# PCB-Neopixel_Control.net
KiCad netlist of a schematic drawn in EAGLE
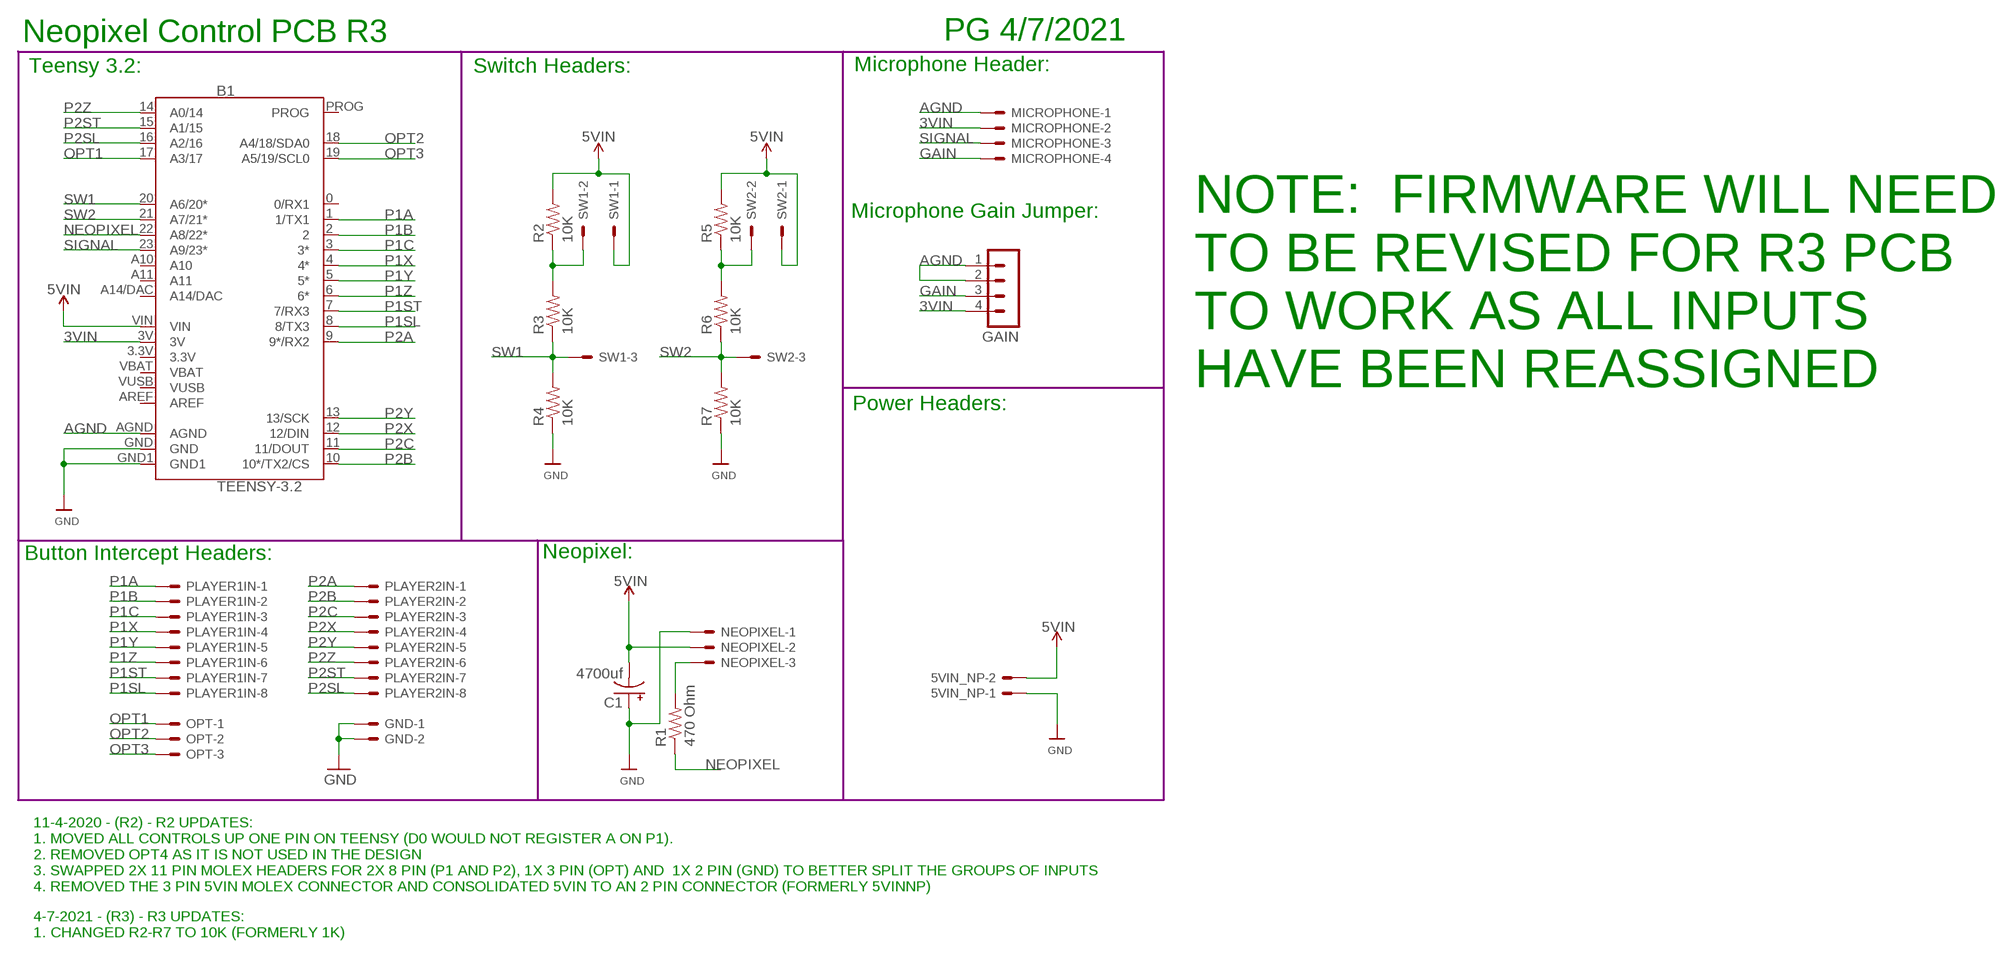
[diagram p0: schematic, sheet 1]

(export (version "E")
  (design (tool "Eeschema 10.0.6"))
  (components
    (comp (ref "5VIN_NP")
      (value "KK-156-2")
      (footprint "eagle-import:KK-156-2")
      (fields (field (name "MF") "MOLEX"))
      (libsource (lib "eagle-import") (part "KK-156-2"))
    )
    (comp (ref "B1")
      (value "TEENSY-3.2")
      (footprint "eagle-import:TEENSY-3.1")
      (libsource (lib "eagle-import") (part "TEENSY-3.1SILK"))
    )
    (comp (ref "C1")
      (value "4700uf")
      (footprint "eagle-import:E5-13")
      (libsource (lib "eagle-import") (part "CPOL-USE5-13"))
    )
    (comp (ref "GAIN")
      (value "MA04-1")
      (footprint "eagle-import:MA04-1")
      (libsource (lib "eagle-import") (part "MA04-1"))
    )
    (comp (ref "GND")
      (value "KK-156-2")
      (footprint "eagle-import:KK-156-2")
      (fields (field (name "MF") "MOLEX"))
      (libsource (lib "eagle-import") (part "KK-156-2"))
    )
    (comp (ref "MICROPHONE")
      (value "KK-156-4")
      (footprint "eagle-import:KK-156-4")
      (fields (field (name "MF") "MOLEX"))
      (libsource (lib "eagle-import") (part "KK-156-4"))
    )
    (comp (ref "NEOPIXEL")
      (value "KK-156-3")
      (footprint "eagle-import:KK-156-3")
      (fields (field (name "MF") "MOLEX"))
      (libsource (lib "eagle-import") (part "KK-156-3"))
    )
    (comp (ref "OPT")
      (value "KK-156-3")
      (footprint "eagle-import:KK-156-3")
      (fields (field (name "MF") "MOLEX"))
      (libsource (lib "eagle-import") (part "KK-156-3"))
    )
    (comp (ref "PLAYER1IN")
      (value "KK-156-8")
      (footprint "eagle-import:KK-156-8")
      (fields (field (name "MF") "MOLEX"))
      (libsource (lib "eagle-import") (part "KK-156-8"))
    )
    (comp (ref "PLAYER2IN")
      (value "KK-156-8")
      (footprint "eagle-import:KK-156-8")
      (fields (field (name "MF") "MOLEX"))
      (libsource (lib "eagle-import") (part "KK-156-8"))
    )
    (comp (ref "R1")
      (value "470 Ohm")
      (footprint "eagle-import:R1206")
      (libsource (lib "eagle-import") (part "R-US_R1206"))
    )
    (comp (ref "R2")
      (value "10K")
      (footprint "eagle-import:R1206")
      (libsource (lib "eagle-import") (part "R-US_R1206"))
    )
    (comp (ref "R3")
      (value "10K")
      (footprint "eagle-import:R1206")
      (libsource (lib "eagle-import") (part "R-US_R1206"))
    )
    (comp (ref "R4")
      (value "10K")
      (footprint "eagle-import:R1206")
      (libsource (lib "eagle-import") (part "R-US_R1206"))
    )
    (comp (ref "R5")
      (value "10K")
      (footprint "eagle-import:R1206")
      (libsource (lib "eagle-import") (part "R-US_R1206"))
    )
    (comp (ref "R6")
      (value "10K")
      (footprint "eagle-import:R1206")
      (libsource (lib "eagle-import") (part "R-US_R1206"))
    )
    (comp (ref "R7")
      (value "10K")
      (footprint "eagle-import:R1206")
      (libsource (lib "eagle-import") (part "R-US_R1206"))
    )
    (comp (ref "SW1")
      (value "KK-156-3")
      (footprint "eagle-import:KK-156-3")
      (fields (field (name "MF") "MOLEX"))
      (libsource (lib "eagle-import") (part "KK-156-3"))
    )
    (comp (ref "SW2")
      (value "KK-156-3")
      (footprint "eagle-import:KK-156-3")
      (fields (field (name "MF") "MOLEX"))
      (libsource (lib "eagle-import") (part "KK-156-3"))
    )
  )
  (nets
    (net (code "1") (name "/3.3V") (class "Default")
      (node (ref "B1") (pin "3.3V") (pinfunction "3.3V_3.3V") (pintype "power_in"))
    )
    (net (code "2") (name "/3VIN") (class "Default")
      (node (ref "B1") (pin "3V") (pinfunction "3V_3V") (pintype "power_in"))
      (node (ref "GAIN") (pin "4") (pinfunction "4_4") (pintype "passive"))
      (node (ref "MICROPHONE") (pin "2") (pinfunction "S_2") (pintype "passive"))
    )
    (net (code "3") (name "/AGND") (class "Default")
      (node (ref "B1") (pin "AGND") (pinfunction "AGND_AGND") (pintype "power_in"))
      (node (ref "GAIN") (pin "1") (pinfunction "1_1") (pintype "passive"))
      (node (ref "GAIN") (pin "2") (pinfunction "2_2") (pintype "passive"))
      (node (ref "MICROPHONE") (pin "1") (pinfunction "S_1") (pintype "passive"))
    )
    (net (code "4") (name "/GAIN") (class "Default")
      (node (ref "GAIN") (pin "3") (pinfunction "3_3") (pintype "passive"))
      (node (ref "MICROPHONE") (pin "4") (pinfunction "S_4") (pintype "passive"))
    )
    (net (code "5") (name "/NEOPIXEL") (class "Default")
      (node (ref "B1") (pin "22") (pinfunction "A8/22*_22") (pintype "bidirectional"))
      (node (ref "R1") (pin "1") (pinfunction "1_1") (pintype "passive"))
    )
    (net (code "6") (name "/OPT1") (class "Default")
      (node (ref "B1") (pin "17") (pinfunction "A3/17_17") (pintype "bidirectional"))
      (node (ref "OPT") (pin "1") (pinfunction "S_1") (pintype "passive"))
    )
    (net (code "7") (name "/OPT2") (class "Default")
      (node (ref "B1") (pin "18") (pinfunction "A4/18/SDA0_18") (pintype "bidirectional"))
      (node (ref "OPT") (pin "2") (pinfunction "S_2") (pintype "passive"))
    )
    (net (code "8") (name "/OPT3") (class "Default")
      (node (ref "B1") (pin "19") (pinfunction "A5/19/SCL0_19") (pintype "bidirectional"))
      (node (ref "OPT") (pin "3") (pinfunction "S_3") (pintype "passive"))
    )
    (net (code "9") (name "/P1A") (class "Default")
      (node (ref "B1") (pin "1") (pinfunction "1/TX1_1") (pintype "bidirectional"))
      (node (ref "PLAYER1IN") (pin "1") (pinfunction "S_1") (pintype "passive"))
    )
    (net (code "10") (name "/P1B") (class "Default")
      (node (ref "B1") (pin "2") (pinfunction "2_2") (pintype "bidirectional"))
      (node (ref "PLAYER1IN") (pin "2") (pinfunction "S_2") (pintype "passive"))
    )
    (net (code "11") (name "/P1C") (class "Default")
      (node (ref "B1") (pin "3") (pinfunction "3*_3") (pintype "bidirectional"))
      (node (ref "PLAYER1IN") (pin "3") (pinfunction "S_3") (pintype "passive"))
    )
    (net (code "12") (name "/P1SL") (class "Default")
      (node (ref "B1") (pin "8") (pinfunction "8/TX3_8") (pintype "bidirectional"))
      (node (ref "PLAYER1IN") (pin "8") (pinfunction "S_8") (pintype "passive"))
    )
    (net (code "13") (name "/P1ST") (class "Default")
      (node (ref "B1") (pin "7") (pinfunction "7/RX3_7") (pintype "bidirectional"))
      (node (ref "PLAYER1IN") (pin "7") (pinfunction "S_7") (pintype "passive"))
    )
    (net (code "14") (name "/P1X") (class "Default")
      (node (ref "B1") (pin "4") (pinfunction "4*_4") (pintype "bidirectional"))
      (node (ref "PLAYER1IN") (pin "4") (pinfunction "S_4") (pintype "passive"))
    )
    (net (code "15") (name "/P1Y") (class "Default")
      (node (ref "B1") (pin "5") (pinfunction "5*_5") (pintype "bidirectional"))
      (node (ref "PLAYER1IN") (pin "5") (pinfunction "S_5") (pintype "passive"))
    )
    (net (code "16") (name "/P1Z") (class "Default")
      (node (ref "B1") (pin "6") (pinfunction "6*_6") (pintype "bidirectional"))
      (node (ref "PLAYER1IN") (pin "6") (pinfunction "S_6") (pintype "passive"))
    )
    (net (code "17") (name "/P2A") (class "Default")
      (node (ref "B1") (pin "9") (pinfunction "9*/RX2_9") (pintype "bidirectional"))
      (node (ref "PLAYER2IN") (pin "1") (pinfunction "S_1") (pintype "passive"))
    )
    (net (code "18") (name "/P2B") (class "Default")
      (node (ref "B1") (pin "10") (pinfunction "10*/TX2/CS_10") (pintype "bidirectional"))
      (node (ref "PLAYER2IN") (pin "2") (pinfunction "S_2") (pintype "passive"))
    )
    (net (code "19") (name "/P2C") (class "Default")
      (node (ref "B1") (pin "11") (pinfunction "11/DOUT_11") (pintype "bidirectional"))
      (node (ref "PLAYER2IN") (pin "3") (pinfunction "S_3") (pintype "passive"))
    )
    (net (code "20") (name "/P2SL") (class "Default")
      (node (ref "B1") (pin "16") (pinfunction "A2/16_16") (pintype "bidirectional"))
      (node (ref "PLAYER2IN") (pin "8") (pinfunction "S_8") (pintype "passive"))
    )
    (net (code "21") (name "/P2ST") (class "Default")
      (node (ref "B1") (pin "15") (pinfunction "A1/15_15") (pintype "bidirectional"))
      (node (ref "PLAYER2IN") (pin "7") (pinfunction "S_7") (pintype "passive"))
    )
    (net (code "22") (name "/P2X") (class "Default")
      (node (ref "B1") (pin "12") (pinfunction "12/DIN_12") (pintype "bidirectional"))
      (node (ref "PLAYER2IN") (pin "4") (pinfunction "S_4") (pintype "passive"))
    )
    (net (code "23") (name "/P2Y") (class "Default")
      (node (ref "B1") (pin "13") (pinfunction "13/SCK_13") (pintype "bidirectional"))
      (node (ref "PLAYER2IN") (pin "5") (pinfunction "S_5") (pintype "passive"))
    )
    (net (code "24") (name "/P2Z") (class "Default")
      (node (ref "B1") (pin "14") (pinfunction "A0/14_14") (pintype "bidirectional"))
      (node (ref "PLAYER2IN") (pin "6") (pinfunction "S_6") (pintype "passive"))
    )
    (net (code "25") (name "/SIGNAL") (class "Default")
      (node (ref "B1") (pin "23") (pinfunction "A9/23*_23") (pintype "bidirectional"))
      (node (ref "MICROPHONE") (pin "3") (pinfunction "S_3") (pintype "passive"))
    )
    (net (code "26") (name "/SW1") (class "Default")
      (node (ref "B1") (pin "20") (pinfunction "A6/20*_20") (pintype "bidirectional"))
      (node (ref "R3") (pin "1") (pinfunction "1_1") (pintype "passive"))
      (node (ref "R4") (pin "2") (pinfunction "2_2") (pintype "passive"))
      (node (ref "SW1") (pin "3") (pinfunction "S_3") (pintype "passive"))
    )
    (net (code "27") (name "/SW2") (class "Default")
      (node (ref "B1") (pin "21") (pinfunction "A7/21*_21") (pintype "bidirectional"))
      (node (ref "R6") (pin "1") (pinfunction "1_1") (pintype "passive"))
      (node (ref "R7") (pin "2") (pinfunction "2_2") (pintype "passive"))
      (node (ref "SW2") (pin "3") (pinfunction "S_3") (pintype "passive"))
    )
    (net (code "28") (name "/VBAT") (class "Default")
      (node (ref "B1") (pin "VBAT") (pinfunction "VBAT_VBAT") (pintype "power_in"))
    )
    (net (code "29") (name "/VUSB") (class "Default")
      (node (ref "B1") (pin "VUSB") (pinfunction "VUSB_VUSB") (pintype "power_in"))
    )
    (net (code "30") (name "5VIN") (class "Default")
      (node (ref "5VIN_NP") (pin "2") (pinfunction "S_2") (pintype "passive"))
      (node (ref "B1") (pin "VIN") (pinfunction "VIN_VIN") (pintype "power_in"))
      (node (ref "C1") (pin "-") (pinfunction "-_-") (pintype "passive"))
      (node (ref "NEOPIXEL") (pin "2") (pinfunction "S_2") (pintype "passive"))
      (node (ref "R2") (pin "2") (pinfunction "2_2") (pintype "passive"))
      (node (ref "R5") (pin "2") (pinfunction "2_2") (pintype "passive"))
      (node (ref "SW1") (pin "1") (pinfunction "S_1") (pintype "passive"))
      (node (ref "SW2") (pin "1") (pinfunction "S_1") (pintype "passive"))
    )
    (net (code "31") (name "GND") (class "Default")
      (node (ref "5VIN_NP") (pin "1") (pinfunction "S_1") (pintype "passive"))
      (node (ref "B1") (pin "GND") (pinfunction "GND_GND") (pintype "power_in"))
      (node (ref "B1") (pin "GND1") (pinfunction "GND1_GND1") (pintype "power_in"))
      (node (ref "C1") (pin "+") (pinfunction "+_+") (pintype "passive"))
      (node (ref "GND") (pin "1") (pinfunction "S_1") (pintype "passive"))
      (node (ref "GND") (pin "2") (pinfunction "S_2") (pintype "passive"))
      (node (ref "NEOPIXEL") (pin "1") (pinfunction "S_1") (pintype "passive"))
      (node (ref "R4") (pin "1") (pinfunction "1_1") (pintype "passive"))
      (node (ref "R7") (pin "1") (pinfunction "1_1") (pintype "passive"))
    )
    (net (code "32") (name "Net-(NEOPIXELC-S)") (class "Default")
      (node (ref "NEOPIXEL") (pin "3") (pinfunction "S_3") (pintype "passive"))
      (node (ref "R1") (pin "2") (pinfunction "2_2") (pintype "passive"))
    )
    (net (code "33") (name "Net-(SW1B-S)") (class "Default")
      (node (ref "R2") (pin "1") (pinfunction "1_1") (pintype "passive"))
      (node (ref "R3") (pin "2") (pinfunction "2_2") (pintype "passive"))
      (node (ref "SW1") (pin "2") (pinfunction "S_2") (pintype "passive"))
    )
    (net (code "34") (name "Net-(SW2B-S)") (class "Default")
      (node (ref "R5") (pin "1") (pinfunction "1_1") (pintype "passive"))
      (node (ref "R6") (pin "2") (pinfunction "2_2") (pintype "passive"))
      (node (ref "SW2") (pin "2") (pinfunction "S_2") (pintype "passive"))
    )
    (net (code "35") (name "unconnected-(B1-0{slash}RX1-Pad0)") (class "Default")
      (node (ref "B1") (pin "0") (pinfunction "0/RX1_0") (pintype "bidirectional"))
    )
    (net (code "36") (name "unconnected-(B1-PadA10)") (class "Default")
      (node (ref "B1") (pin "A10") (pinfunction "A10_A10") (pintype "bidirectional"))
    )
    (net (code "37") (name "unconnected-(B1-PadA11)") (class "Default")
      (node (ref "B1") (pin "A11") (pinfunction "A11_A11") (pintype "bidirectional"))
    )
    (net (code "38") (name "unconnected-(B1-PadA14{slash}DAC)") (class "Default")
      (node (ref "B1") (pin "A14/DAC") (pinfunction "A14/DAC_A14/DAC") (pintype "bidirectional"))
    )
    (net (code "39") (name "unconnected-(B1-PadAREF)") (class "Default")
      (node (ref "B1") (pin "AREF") (pinfunction "AREF_AREF") (pintype "bidirectional"))
    )
    (net (code "40") (name "unconnected-(B1-PadPROG)") (class "Default")
      (node (ref "B1") (pin "PROG") (pinfunction "PROG_PROG") (pintype "bidirectional"))
    )
  )
)
